# Due_RS422_Transceiver.net
KiCad netlist of a schematic drawn in EAGLE
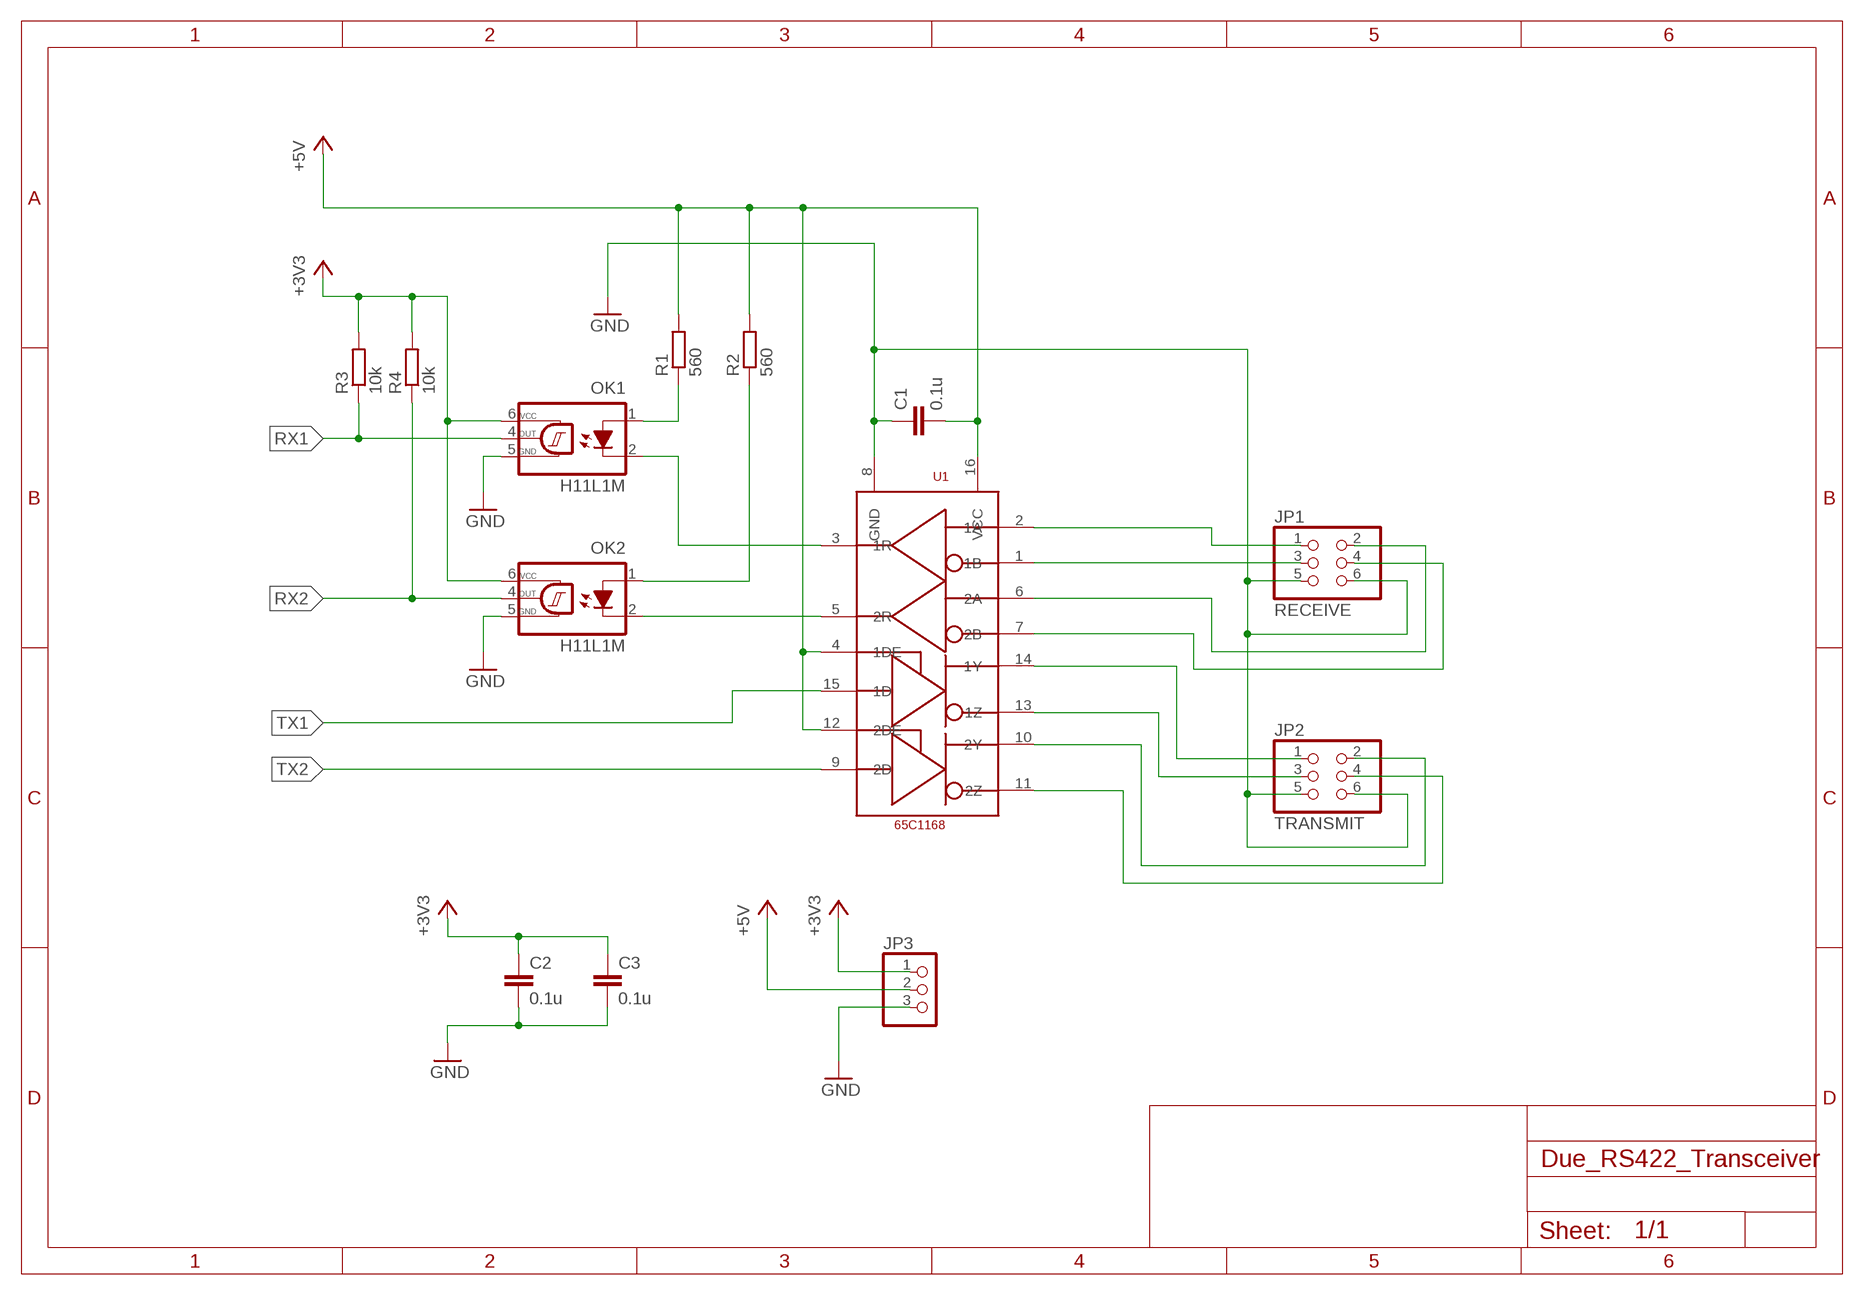
[diagram p0: schematic, sheet 1]

(export (version "E")
  (design (tool "Eeschema 10.0.6"))
  (components
    (comp (ref "C1")
      (value "0.1u")
      (footprint "eagle-import:C050-030X075")
      (libsource (lib "eagle-import") (part "C-EU050-030X075"))
    )
    (comp (ref "C2")
      (value "0.1u")
      (footprint "eagle-import:C050-030X075")
      (libsource (lib "eagle-import") (part "C-EU050-030X075"))
    )
    (comp (ref "C3")
      (value "0.1u")
      (footprint "eagle-import:C050-030X075")
      (libsource (lib "eagle-import") (part "C-EU050-030X075"))
    )
    (comp (ref "JP1")
      (value "RECEIVE")
      (footprint "eagle-import:2X03")
      (libsource (lib "eagle-import") (part "PINHD-2X3"))
    )
    (comp (ref "JP2")
      (value "TRANSMIT")
      (footprint "eagle-import:2X03")
      (libsource (lib "eagle-import") (part "PINHD-2X3"))
    )
    (comp (ref "JP3")
      (value "PINHD-1X3")
      (footprint "eagle-import:1X03")
      (libsource (lib "eagle-import") (part "PINHD-1X3"))
    )
    (comp (ref "OK1")
      (value "H11L1M")
      (footprint "eagle-import:DIL06")
      (fields (field (name "MF") "FAIRCHILD SEMICONDUCTOR") (field (name "MPN") "H11L1-M"))
      (libsource (lib "eagle-import") (part "H11LM1"))
    )
    (comp (ref "OK2")
      (value "H11L1M")
      (footprint "eagle-import:DIL06")
      (fields (field (name "MF") "FAIRCHILD SEMICONDUCTOR") (field (name "MPN") "H11L1-M"))
      (libsource (lib "eagle-import") (part "H11LM1"))
    )
    (comp (ref "R1")
      (value "560")
      (footprint "eagle-import:0204_7")
      (libsource (lib "eagle-import") (part "R-EU_0204/7"))
    )
    (comp (ref "R2")
      (value "560")
      (footprint "eagle-import:0204_7")
      (libsource (lib "eagle-import") (part "R-EU_0204/7"))
    )
    (comp (ref "R3")
      (value "10k")
      (footprint "eagle-import:0204_7")
      (libsource (lib "eagle-import") (part "R-EU_0204/7"))
    )
    (comp (ref "R4")
      (value "10k")
      (footprint "eagle-import:0204_7")
      (libsource (lib "eagle-import") (part "R-EU_0204/7"))
    )
    (comp (ref "U1")
      (value "65C1168")
      (footprint "eagle-import:DIP16")
      (libsource (lib "eagle-import") (part "SN65C1168"))
    )
  )
  (nets
    (net (code "1") (name "+3V3") (class "Default")
      (node (ref "C2") (pin "1") (pinfunction "1_1") (pintype "passive"))
      (node (ref "C3") (pin "1") (pinfunction "1_1") (pintype "passive"))
      (node (ref "JP3") (pin "1") (pinfunction "1_1") (pintype "passive"))
      (node (ref "OK1") (pin "6") (pinfunction "VCC_6") (pintype "power_in"))
      (node (ref "OK2") (pin "6") (pinfunction "VCC_6") (pintype "power_in"))
      (node (ref "R3") (pin "2") (pinfunction "2_2") (pintype "passive"))
      (node (ref "R4") (pin "2") (pinfunction "2_2") (pintype "passive"))
    )
    (net (code "2") (name "+5V") (class "Default")
      (node (ref "C1") (pin "2") (pinfunction "2_2") (pintype "passive"))
      (node (ref "JP3") (pin "2") (pinfunction "2_2") (pintype "passive"))
      (node (ref "R1") (pin "2") (pinfunction "2_2") (pintype "passive"))
      (node (ref "R2") (pin "2") (pinfunction "2_2") (pintype "passive"))
      (node (ref "U1") (pin "12") (pinfunction "2DE_12") (pintype "bidirectional"))
      (node (ref "U1") (pin "16") (pinfunction "VCC_16") (pintype "bidirectional"))
      (node (ref "U1") (pin "4") (pinfunction "1DE_4") (pintype "bidirectional"))
    )
    (net (code "3") (name "GND") (class "Default")
      (node (ref "C1") (pin "1") (pinfunction "1_1") (pintype "passive"))
      (node (ref "C2") (pin "2") (pinfunction "2_2") (pintype "passive"))
      (node (ref "C3") (pin "2") (pinfunction "2_2") (pintype "passive"))
      (node (ref "JP1") (pin "5") (pinfunction "5_5") (pintype "passive"))
      (node (ref "JP1") (pin "6") (pinfunction "6_6") (pintype "passive"))
      (node (ref "JP2") (pin "5") (pinfunction "5_5") (pintype "passive"))
      (node (ref "JP2") (pin "6") (pinfunction "6_6") (pintype "passive"))
      (node (ref "JP3") (pin "3") (pinfunction "3_3") (pintype "passive"))
      (node (ref "OK1") (pin "5") (pinfunction "GND_5") (pintype "power_in"))
      (node (ref "OK2") (pin "5") (pinfunction "GND_5") (pintype "power_in"))
      (node (ref "U1") (pin "8") (pinfunction "GND_8") (pintype "bidirectional"))
    )
    (net (code "4") (name "Net-(OK1-A)") (class "Default")
      (node (ref "OK1") (pin "1") (pinfunction "A_1") (pintype "passive"))
      (node (ref "R1") (pin "1") (pinfunction "1_1") (pintype "passive"))
    )
    (net (code "5") (name "Net-(OK1-C)") (class "Default")
      (node (ref "OK1") (pin "2") (pinfunction "C_2") (pintype "passive"))
      (node (ref "U1") (pin "3") (pinfunction "1R_3") (pintype "bidirectional"))
    )
    (net (code "6") (name "Net-(OK2-A)") (class "Default")
      (node (ref "OK2") (pin "1") (pinfunction "A_1") (pintype "passive"))
      (node (ref "R2") (pin "1") (pinfunction "1_1") (pintype "passive"))
    )
    (net (code "7") (name "Net-(OK2-C)") (class "Default")
      (node (ref "OK2") (pin "2") (pinfunction "C_2") (pintype "passive"))
      (node (ref "U1") (pin "5") (pinfunction "2R_5") (pintype "bidirectional"))
    )
    (net (code "8") (name "Net-(U1-1A)") (class "Default")
      (node (ref "JP1") (pin "1") (pinfunction "1_1") (pintype "passive"))
      (node (ref "U1") (pin "2") (pinfunction "1A_2") (pintype "bidirectional"))
    )
    (net (code "9") (name "Net-(U1-1B)") (class "Default")
      (node (ref "JP1") (pin "3") (pinfunction "3_3") (pintype "passive"))
      (node (ref "U1") (pin "1") (pinfunction "1B_1") (pintype "bidirectional"))
    )
    (net (code "10") (name "Net-(U1-1Y)") (class "Default")
      (node (ref "JP2") (pin "1") (pinfunction "1_1") (pintype "passive"))
      (node (ref "U1") (pin "14") (pinfunction "1Y_14") (pintype "bidirectional"))
    )
    (net (code "11") (name "Net-(U1-1Z)") (class "Default")
      (node (ref "JP2") (pin "3") (pinfunction "3_3") (pintype "passive"))
      (node (ref "U1") (pin "13") (pinfunction "1Z_13") (pintype "bidirectional"))
    )
    (net (code "12") (name "Net-(U1-2A)") (class "Default")
      (node (ref "JP1") (pin "2") (pinfunction "2_2") (pintype "passive"))
      (node (ref "U1") (pin "6") (pinfunction "2A_6") (pintype "bidirectional"))
    )
    (net (code "13") (name "Net-(U1-2B)") (class "Default")
      (node (ref "JP1") (pin "4") (pinfunction "4_4") (pintype "passive"))
      (node (ref "U1") (pin "7") (pinfunction "2B_7") (pintype "bidirectional"))
    )
    (net (code "14") (name "Net-(U1-2Y)") (class "Default")
      (node (ref "JP2") (pin "2") (pinfunction "2_2") (pintype "passive"))
      (node (ref "U1") (pin "10") (pinfunction "2Y_10") (pintype "bidirectional"))
    )
    (net (code "15") (name "Net-(U1-2Z)") (class "Default")
      (node (ref "JP2") (pin "4") (pinfunction "4_4") (pintype "passive"))
      (node (ref "U1") (pin "11") (pinfunction "2Z_11") (pintype "bidirectional"))
    )
    (net (code "16") (name "RX1") (class "Default")
      (node (ref "OK1") (pin "4") (pinfunction "OUT_4") (pintype "output"))
      (node (ref "R3") (pin "1") (pinfunction "1_1") (pintype "passive"))
    )
    (net (code "17") (name "RX2") (class "Default")
      (node (ref "OK2") (pin "4") (pinfunction "OUT_4") (pintype "output"))
      (node (ref "R4") (pin "1") (pinfunction "1_1") (pintype "passive"))
    )
    (net (code "18") (name "TX1") (class "Default")
      (node (ref "U1") (pin "15") (pinfunction "1D_15") (pintype "bidirectional"))
    )
    (net (code "19") (name "TX2") (class "Default")
      (node (ref "U1") (pin "9") (pinfunction "2D_9") (pintype "bidirectional"))
    )
  )
)
